# ATTiny85_5LED_R2.net
KiCad netlist of a schematic drawn in EAGLE
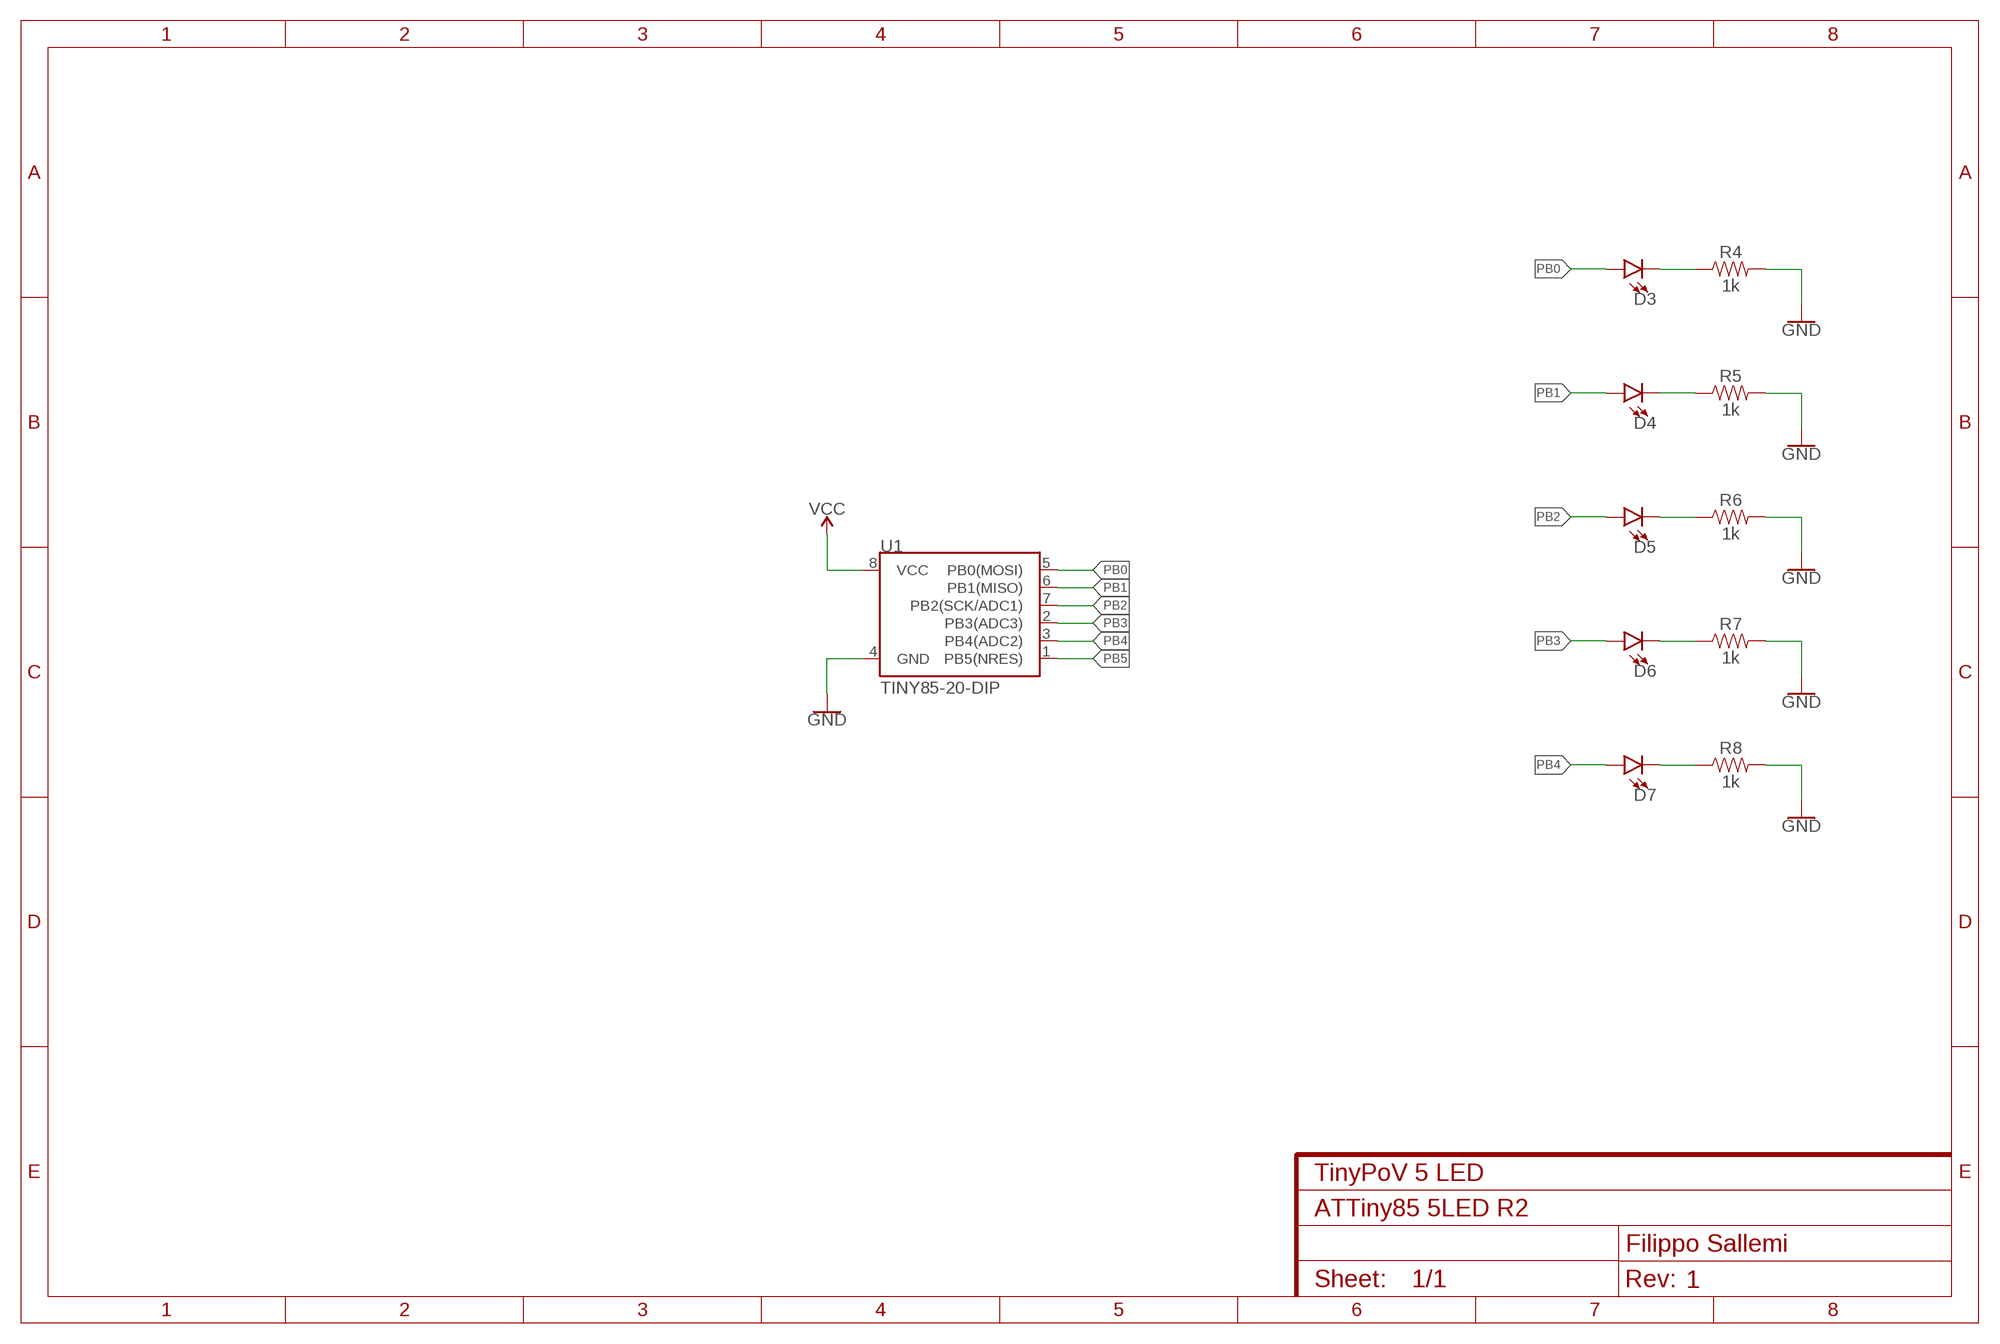
[diagram p0: schematic, sheet 1]

(export (version "E")
  (design (tool "Eeschema 10.0.6"))
  (components
    (comp (ref "D3")
      (value "LED5MM")
      (footprint "eagle-import:LED_5MM")
      (libsource (lib "eagle-import") (part "LED5MM"))
    )
    (comp (ref "D4")
      (value "LED5MM")
      (footprint "eagle-import:LED_5MM")
      (libsource (lib "eagle-import") (part "LED5MM"))
    )
    (comp (ref "D5")
      (value "LED5MM")
      (footprint "eagle-import:LED_5MM")
      (libsource (lib "eagle-import") (part "LED5MM"))
    )
    (comp (ref "D6")
      (value "LED5MM")
      (footprint "eagle-import:LED_5MM")
      (libsource (lib "eagle-import") (part "LED5MM"))
    )
    (comp (ref "D7")
      (value "LED5MM")
      (footprint "eagle-import:LED_5MM")
      (libsource (lib "eagle-import") (part "LED5MM"))
    )
    (comp (ref "R4")
      (value "1k")
      (footprint "eagle-import:AXIAL-0.3")
      (libsource (lib "eagle-import") (part "1KOHM-HORIZ-1/4W-5%"))
    )
    (comp (ref "R5")
      (value "1k")
      (footprint "eagle-import:AXIAL-0.3")
      (libsource (lib "eagle-import") (part "1KOHM-HORIZ-1/4W-5%"))
    )
    (comp (ref "R6")
      (value "1k")
      (footprint "eagle-import:AXIAL-0.3")
      (libsource (lib "eagle-import") (part "1KOHM-HORIZ-1/4W-5%"))
    )
    (comp (ref "R7")
      (value "1k")
      (footprint "eagle-import:AXIAL-0.3")
      (libsource (lib "eagle-import") (part "1KOHM-HORIZ-1/4W-5%"))
    )
    (comp (ref "R8")
      (value "1k")
      (footprint "eagle-import:AXIAL-0.3")
      (libsource (lib "eagle-import") (part "1KOHM-HORIZ-1/4W-5%"))
    )
    (comp (ref "U1")
      (value "TINY85-20-DIP")
      (footprint "eagle-import:DIP08_MCU")
      (libsource (lib "eagle-import") (part "ATTINY45TINY85-20-DIP"))
    )
  )
  (nets
    (net (code "1") (name "GND") (class "Default")
      (node (ref "R4") (pin "P$2") (pinfunction "2_P$2") (pintype "passive"))
      (node (ref "R5") (pin "P$2") (pinfunction "2_P$2") (pintype "passive"))
      (node (ref "R6") (pin "P$2") (pinfunction "2_P$2") (pintype "passive"))
      (node (ref "R7") (pin "P$2") (pinfunction "2_P$2") (pintype "passive"))
      (node (ref "R8") (pin "P$2") (pinfunction "2_P$2") (pintype "passive"))
      (node (ref "U1") (pin "4") (pinfunction "GND_4") (pintype "bidirectional"))
    )
    (net (code "2") (name "Net-(D3-C)") (class "Default")
      (node (ref "D3") (pin "K") (pinfunction "C_K") (pintype "passive"))
      (node (ref "R4") (pin "P$1") (pinfunction "1_P$1") (pintype "passive"))
    )
    (net (code "3") (name "Net-(D4-C)") (class "Default")
      (node (ref "D4") (pin "K") (pinfunction "C_K") (pintype "passive"))
      (node (ref "R5") (pin "P$1") (pinfunction "1_P$1") (pintype "passive"))
    )
    (net (code "4") (name "Net-(D5-C)") (class "Default")
      (node (ref "D5") (pin "K") (pinfunction "C_K") (pintype "passive"))
      (node (ref "R6") (pin "P$1") (pinfunction "1_P$1") (pintype "passive"))
    )
    (net (code "5") (name "Net-(D6-C)") (class "Default")
      (node (ref "D6") (pin "K") (pinfunction "C_K") (pintype "passive"))
      (node (ref "R7") (pin "P$1") (pinfunction "1_P$1") (pintype "passive"))
    )
    (net (code "6") (name "Net-(D7-C)") (class "Default")
      (node (ref "D7") (pin "K") (pinfunction "C_K") (pintype "passive"))
      (node (ref "R8") (pin "P$1") (pinfunction "1_P$1") (pintype "passive"))
    )
    (net (code "7") (name "PB0") (class "Default")
      (node (ref "D3") (pin "A") (pinfunction "A_A") (pintype "passive"))
      (node (ref "U1") (pin "5") (pinfunction "PB0(MOSI)_5") (pintype "bidirectional"))
    )
    (net (code "8") (name "PB1") (class "Default")
      (node (ref "D4") (pin "A") (pinfunction "A_A") (pintype "passive"))
      (node (ref "U1") (pin "6") (pinfunction "PB1(MISO)_6") (pintype "bidirectional"))
    )
    (net (code "9") (name "PB2") (class "Default")
      (node (ref "D5") (pin "A") (pinfunction "A_A") (pintype "passive"))
      (node (ref "U1") (pin "7") (pinfunction "PB2(SCK/ADC1)_7") (pintype "bidirectional"))
    )
    (net (code "10") (name "PB3") (class "Default")
      (node (ref "D6") (pin "A") (pinfunction "A_A") (pintype "passive"))
      (node (ref "U1") (pin "2") (pinfunction "PB3(ADC3)_2") (pintype "bidirectional"))
    )
    (net (code "11") (name "PB4") (class "Default")
      (node (ref "D7") (pin "A") (pinfunction "A_A") (pintype "passive"))
      (node (ref "U1") (pin "3") (pinfunction "PB4(ADC2)_3") (pintype "bidirectional"))
    )
    (net (code "12") (name "PB5") (class "Default")
      (node (ref "U1") (pin "1") (pinfunction "PB5(NRES)_1") (pintype "bidirectional"))
    )
    (net (code "13") (name "VCC") (class "Default")
      (node (ref "U1") (pin "8") (pinfunction "VCC_8") (pintype "bidirectional"))
    )
  )
)
